# osccds.net
KiCad netlist of a schematic drawn in EAGLE
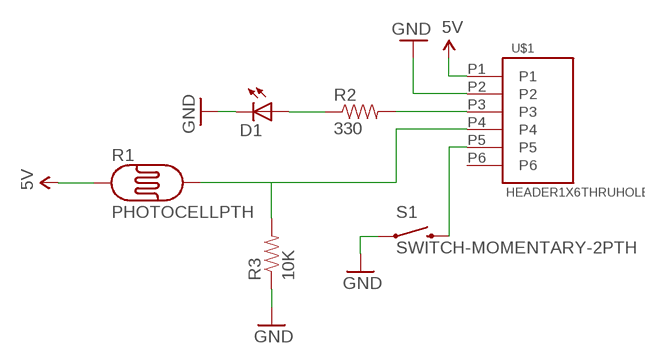
[diagram p0: schematic, sheet 1]

(export (version "E")
  (design (tool "Eeschema 10.0.6"))
  (components
    (comp (ref "D1")
      (value "LED3MM")
      (footprint "eagle-import:LED3MM")
      (libsource (lib "eagle-import") (part "LED3MM"))
    )
    (comp (ref "R1")
      (value "PHOTOCELLPTH")
      (footprint "eagle-import:PHOTOCELL")
      (libsource (lib "eagle-import") (part "PHOTOCELLPTH"))
    )
    (comp (ref "R2")
      (value "330")
      (footprint "eagle-import:AXIAL-0.3")
      (libsource (lib "eagle-import") (part "RESISTORPTH1"))
    )
    (comp (ref "R3")
      (value "10K")
      (footprint "eagle-import:AXIAL-0.3")
      (libsource (lib "eagle-import") (part "RESISTORPTH1"))
    )
    (comp (ref "S1")
      (value "SWITCH-MOMENTARY-2PTH")
      (footprint "eagle-import:TACTILE-PTH")
      (libsource (lib "eagle-import") (part "SWITCH-MOMENTARY-2PTH"))
    )
    (comp (ref "U$1")
      (value "HEADER1X6THRUHOLE")
      (footprint "eagle-import:HEADER1X6-TH")
      (libsource (lib "eagle-import") (part "HEADER1X6THRUHOLE"))
    )
  )
  (nets
    (net (code "1") (name "5V") (class "Default")
      (node (ref "R1") (pin "1") (pinfunction "P$1_1") (pintype "bidirectional"))
      (node (ref "U$1") (pin "P1") (pinfunction "P1_P1") (pintype "bidirectional"))
    )
    (net (code "2") (name "GND") (class "Default")
      (node (ref "D1") (pin "K") (pinfunction "C_K") (pintype "passive"))
      (node (ref "R3") (pin "P$1") (pinfunction "1_P$1") (pintype "passive"))
      (node (ref "S1") (pin "1") (pinfunction "1_1") (pintype "passive"))
      (node (ref "U$1") (pin "P2") (pinfunction "P2_P2") (pintype "bidirectional"))
    )
    (net (code "3") (name "Net-(R1-P$2)") (class "Default")
      (node (ref "R1") (pin "2") (pinfunction "P$2_2") (pintype "bidirectional"))
      (node (ref "R3") (pin "P$2") (pinfunction "2_P$2") (pintype "passive"))
      (node (ref "U$1") (pin "P4") (pinfunction "P4_P4") (pintype "bidirectional"))
    )
    (net (code "4") (name "Net-(R2-1)") (class "Default")
      (node (ref "D1") (pin "A") (pinfunction "A_A") (pintype "passive"))
      (node (ref "R2") (pin "P$1") (pinfunction "1_P$1") (pintype "passive"))
    )
    (net (code "5") (name "Net-(R2-2)") (class "Default")
      (node (ref "R2") (pin "P$2") (pinfunction "2_P$2") (pintype "passive"))
      (node (ref "U$1") (pin "P3") (pinfunction "P3_P3") (pintype "bidirectional"))
    )
    (net (code "6") (name "Net-(S1-2)") (class "Default")
      (node (ref "S1") (pin "3") (pinfunction "2_3") (pintype "passive"))
      (node (ref "U$1") (pin "P5") (pinfunction "P5_P5") (pintype "bidirectional"))
    )
    (net (code "7") (name "unconnected-(U$1-PadP6)") (class "Default")
      (node (ref "U$1") (pin "P6") (pinfunction "P6_P6") (pintype "bidirectional"))
    )
  )
)
